# Electrobrdv3.net
KiCad netlist of a schematic drawn in EAGLE
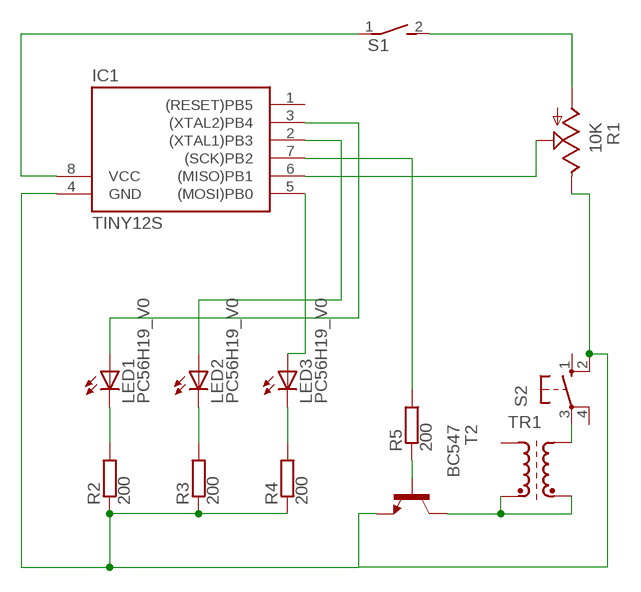
[diagram p0: schematic, sheet 1]

(export (version "E")
  (design (tool "Eeschema 10.0.6"))
  (components
    (comp (ref "IC1")
      (value "TINY12S")
      (footprint "eagle-import:SOIC8")
      (libsource (lib "eagle-import") (part "TINY12S"))
    )
    (comp (ref "LED1")
      (value "PC56H19_V0")
      (footprint "eagle-import:PC56H19_V0")
      (libsource (lib "eagle-import") (part "PC56H19_V0"))
    )
    (comp (ref "LED2")
      (value "PC56H19_V0")
      (footprint "eagle-import:PC56H19_V0")
      (libsource (lib "eagle-import") (part "PC56H19_V0"))
    )
    (comp (ref "LED3")
      (value "PC56H19_V0")
      (footprint "eagle-import:PC56H19_V0")
      (libsource (lib "eagle-import") (part "PC56H19_V0"))
    )
    (comp (ref "R1")
      (value "10K")
      (footprint "eagle-import:PT-SPIN")
      (libsource (lib "eagle-import") (part "TRIM_US-PTSPIN"))
    )
    (comp (ref "R2")
      (value "200")
      (footprint "eagle-import:SMK")
      (libsource (lib "eagle-import") (part "SMK"))
    )
    (comp (ref "R3")
      (value "200")
      (footprint "eagle-import:SMK")
      (libsource (lib "eagle-import") (part "SMK"))
    )
    (comp (ref "R4")
      (value "200")
      (footprint "eagle-import:SMK")
      (libsource (lib "eagle-import") (part "SMK"))
    )
    (comp (ref "R5")
      (value "200")
      (footprint "eagle-import:SMK")
      (libsource (lib "eagle-import") (part "SMK"))
    )
    (comp (ref "S1")
      (value "DS01E")
      (footprint "eagle-import:DS-01")
      (libsource (lib "eagle-import") (part "DS01E"))
    )
    (comp (ref "S2")
      (value "10-XX")
      (footprint "eagle-import:B3F-10XX")
      (fields (field (name "MPN") "B3F-1000"))
      (libsource (lib "eagle-import") (part "10-XX"))
    )
    (comp (ref "T2")
      (value "BC547")
      (footprint "eagle-import:TO92")
      (libsource (lib "eagle-import") (part "BC547"))
    )
    (comp (ref "TR1")
      (value "SM-T4")
      (footprint "eagle-import:SM-T4")
      (libsource (lib "eagle-import") (part "SM-T4"))
    )
  )
  (nets
    (net (code "1") (name "Net-(IC1-(MISO)PB1)") (class "Default")
      (node (ref "IC1") (pin "6") (pinfunction "(MISO)PB1_6") (pintype "bidirectional"))
      (node (ref "R1") (pin "S") (pinfunction "S_S") (pintype "passive"))
    )
    (net (code "2") (name "Net-(IC1-(MOSI)PB0)") (class "Default")
      (node (ref "IC1") (pin "5") (pinfunction "(MOSI)PB0_5") (pintype "bidirectional"))
      (node (ref "LED3") (pin "2") (pinfunction "A_2") (pintype "passive"))
      (node (ref "LED3") (pin "4") (pinfunction "A_4") (pintype "passive"))
    )
    (net (code "3") (name "Net-(IC1-(SCK)PB2)") (class "Default")
      (node (ref "IC1") (pin "7") (pinfunction "(SCK)PB2_7") (pintype "bidirectional"))
      (node (ref "R5") (pin "1") (pinfunction "1_1") (pintype "passive"))
    )
    (net (code "4") (name "Net-(IC1-(XTAL1)PB3)") (class "Default")
      (node (ref "IC1") (pin "2") (pinfunction "(XTAL1)PB3_2") (pintype "bidirectional"))
      (node (ref "LED2") (pin "2") (pinfunction "A_2") (pintype "passive"))
      (node (ref "LED2") (pin "4") (pinfunction "A_4") (pintype "passive"))
    )
    (net (code "5") (name "Net-(IC1-(XTAL2)PB4)") (class "Default")
      (node (ref "IC1") (pin "3") (pinfunction "(XTAL2)PB4_3") (pintype "bidirectional"))
      (node (ref "LED1") (pin "2") (pinfunction "A_2") (pintype "passive"))
      (node (ref "LED1") (pin "4") (pinfunction "A_4") (pintype "passive"))
    )
    (net (code "6") (name "Net-(IC1-GND)") (class "Default")
      (node (ref "IC1") (pin "4") (pinfunction "GND_4") (pintype "power_in"))
      (node (ref "R1") (pin "E") (pinfunction "E_E") (pintype "passive"))
      (node (ref "R2") (pin "2") (pinfunction "2_2") (pintype "passive"))
      (node (ref "R3") (pin "2") (pinfunction "2_2") (pintype "passive"))
      (node (ref "R4") (pin "2") (pinfunction "2_2") (pintype "passive"))
      (node (ref "S2") (pin "2") (pinfunction "S1_2") (pintype "passive"))
      (node (ref "T2") (pin "1") (pinfunction "E_1") (pintype "passive"))
    )
    (net (code "7") (name "Net-(IC1-VCC)") (class "Default")
      (node (ref "IC1") (pin "8") (pinfunction "VCC_8") (pintype "power_in"))
      (node (ref "S1") (pin "1") (pinfunction "1_1") (pintype "passive"))
    )
    (net (code "8") (name "Net-(LED1-C-Pad1)") (class "Default")
      (node (ref "LED1") (pin "1") (pinfunction "C_1") (pintype "passive"))
      (node (ref "LED1") (pin "3") (pinfunction "C_3") (pintype "passive"))
      (node (ref "R2") (pin "1") (pinfunction "1_1") (pintype "passive"))
    )
    (net (code "9") (name "Net-(LED2-C-Pad1)") (class "Default")
      (node (ref "LED2") (pin "1") (pinfunction "C_1") (pintype "passive"))
      (node (ref "LED2") (pin "3") (pinfunction "C_3") (pintype "passive"))
      (node (ref "R3") (pin "1") (pinfunction "1_1") (pintype "passive"))
    )
    (net (code "10") (name "Net-(LED3-C-Pad1)") (class "Default")
      (node (ref "LED3") (pin "1") (pinfunction "C_1") (pintype "passive"))
      (node (ref "LED3") (pin "3") (pinfunction "C_3") (pintype "passive"))
      (node (ref "R4") (pin "1") (pinfunction "1_1") (pintype "passive"))
    )
    (net (code "11") (name "Net-(R1-PadA)") (class "Default")
      (node (ref "R1") (pin "A") (pinfunction "A_A") (pintype "passive"))
      (node (ref "S1") (pin "2") (pinfunction "2_2") (pintype "passive"))
    )
    (net (code "12") (name "Net-(S2-P)") (class "Default")
      (node (ref "S2") (pin "3") (pinfunction "P_3") (pintype "passive"))
      (node (ref "TR1") (pin "5") (pinfunction "A2_5") (pintype "passive"))
    )
    (net (code "13") (name "Net-(T2-B)") (class "Default")
      (node (ref "R5") (pin "2") (pinfunction "2_2") (pintype "passive"))
      (node (ref "T2") (pin "2") (pinfunction "B_2") (pintype "passive"))
    )
    (net (code "14") (name "Net-(T2-C)") (class "Default")
      (node (ref "T2") (pin "3") (pinfunction "C_3") (pintype "passive"))
      (node (ref "TR1") (pin "2") (pinfunction "E1_2") (pintype "passive"))
      (node (ref "TR1") (pin "4") (pinfunction "E2_4") (pintype "passive"))
    )
    (net (code "15") (name "unconnected-(IC1-(RESET)PB5-Pad1)") (class "Default")
      (node (ref "IC1") (pin "1") (pinfunction "(RESET)PB5_1") (pintype "bidirectional"))
    )
    (net (code "16") (name "unconnected-(S2-P1-Pad4)") (class "Default")
      (node (ref "S2") (pin "4") (pinfunction "P1_4") (pintype "passive"))
    )
    (net (code "17") (name "unconnected-(S2-S-Pad1)") (class "Default")
      (node (ref "S2") (pin "1") (pinfunction "S_1") (pintype "passive"))
    )
    (net (code "18") (name "unconnected-(TR1-A1-Pad1)") (class "Default")
      (node (ref "TR1") (pin "1") (pinfunction "A1_1") (pintype "passive"))
    )
  )
)
